# Connectors-MK2.net
KiCad netlist of a schematic drawn in EAGLE
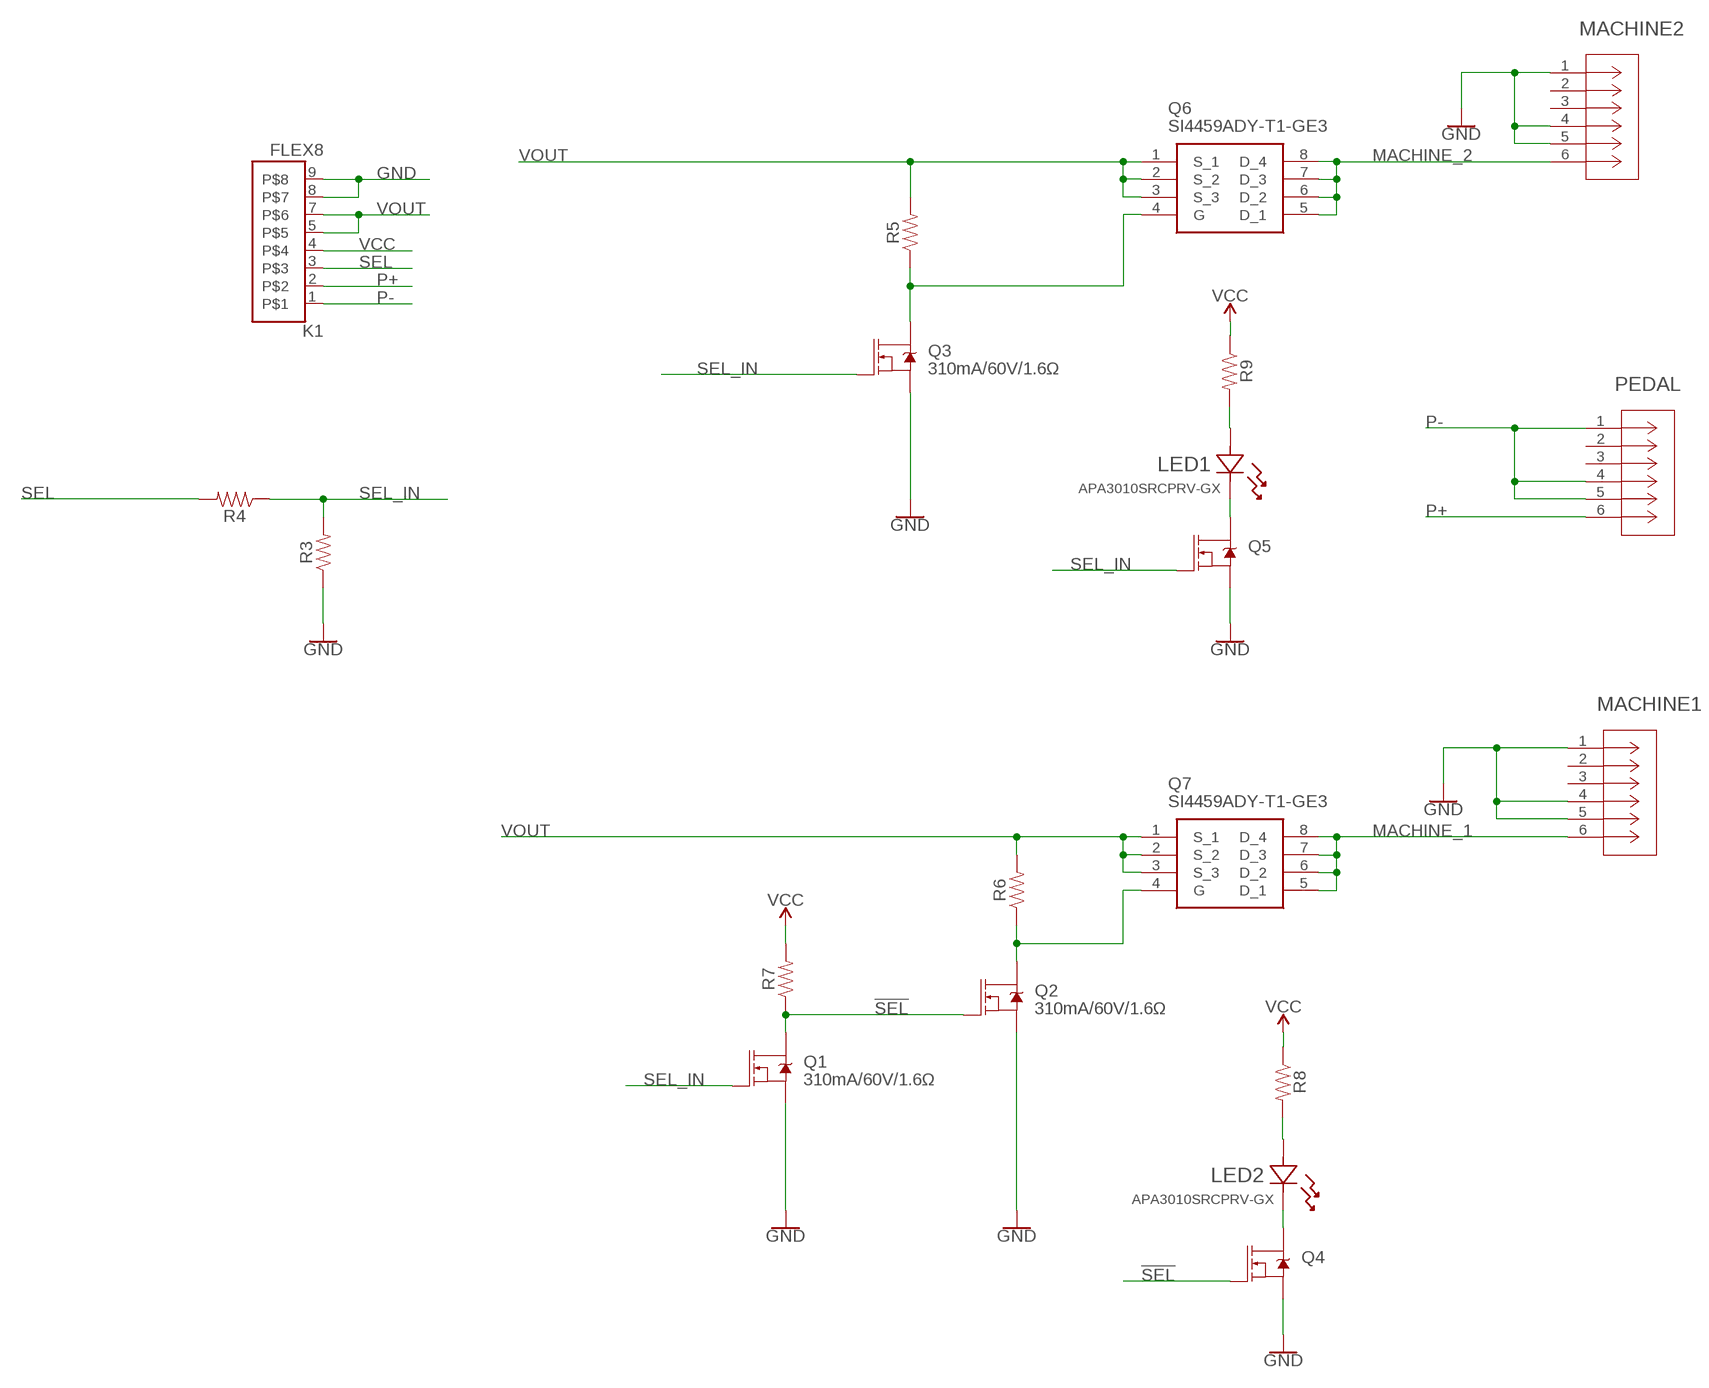
[diagram p0: schematic, sheet 1]

(export (version "E")
  (design (tool "Eeschema 10.0.6"))
  (components
    (comp (ref "K1")
      (value "FLEX8")
      (footprint "eagle-import:FLEX8")
      (libsource (lib "eagle-import") (part "FLEX8"))
    )
    (comp (ref "LED1")
      (value "APA3010SRCPRV-GX")
      (footprint "eagle-import:LED_APA3010SRCPRV-GX_KNB")
      (fields (field (name "COPYRIGHT") "Copyright (C) 2018 Accelerated Designs. All rights reserved"))
      (libsource (lib "eagle-import") (part "APA3010SRCPRV-GX"))
    )
    (comp (ref "LED2")
      (value "APA3010SRCPRV-GX")
      (footprint "eagle-import:LED_APA3010SRCPRV-GX_KNB")
      (fields (field (name "COPYRIGHT") "Copyright (C) 2018 Accelerated Designs. All rights reserved"))
      (libsource (lib "eagle-import") (part "APA3010SRCPRV-GX"))
    )
    (comp (ref "MACHINE1")
      (value "ACJS-MHDR")
      (footprint "eagle-import:CONN_MHDR_AMP")
      (fields (field (name "COPYRIGHT") "Copyright (C) 2018 Accelerated Designs. All rights reserved"))
      (libsource (lib "eagle-import") (part "ACJS-MHDR"))
    )
    (comp (ref "MACHINE2")
      (value "ACJS-MHDR")
      (footprint "eagle-import:CONN_MHDR_AMP")
      (fields (field (name "COPYRIGHT") "Copyright (C) 2018 Accelerated Designs. All rights reserved"))
      (libsource (lib "eagle-import") (part "ACJS-MHDR"))
    )
    (comp (ref "PEDAL")
      (value "ACJS-MHDR")
      (footprint "eagle-import:CONN_MHDR_AMP")
      (fields (field (name "COPYRIGHT") "Copyright (C) 2018 Accelerated Designs. All rights reserved"))
      (libsource (lib "eagle-import") (part "ACJS-MHDR"))
    )
    (comp (ref "Q1")
      (value "310mA/60V/1.6Ω")
      (footprint "eagle-import:SOT323")
      (libsource (lib "eagle-import") (part "MOSFET-NCH-2N7002PW"))
    )
    (comp (ref "Q2")
      (value "310mA/60V/1.6Ω")
      (footprint "eagle-import:SOT323")
      (libsource (lib "eagle-import") (part "MOSFET-NCH-2N7002PW"))
    )
    (comp (ref "Q3")
      (value "310mA/60V/1.6Ω")
      (footprint "eagle-import:SOT323")
      (libsource (lib "eagle-import") (part "MOSFET-NCH-2N7002PW"))
    )
    (comp (ref "Q4")
      (value "310mA/60V/1.6Ω")
      (footprint "eagle-import:SOT323")
      (libsource (lib "eagle-import") (part "MOSFET-NCH-2N7002PW"))
    )
    (comp (ref "Q5")
      (value "310mA/60V/1.6Ω")
      (footprint "eagle-import:SOT323")
      (libsource (lib "eagle-import") (part "MOSFET-NCH-2N7002PW"))
    )
    (comp (ref "Q6")
      (value "SI4459ADY-T1-GE3")
      (footprint "eagle-import:SOIC127P600X175-8N")
      (fields (field (name "MOUSER_PART_NUMBER") "781-SI4459ADY-T1-GE3"))
      (libsource (lib "eagle-import") (part "SI4459ADY-T1-GE3"))
    )
    (comp (ref "Q7")
      (value "SI4459ADY-T1-GE3")
      (footprint "eagle-import:SOIC127P600X175-8N")
      (fields (field (name "MOUSER_PART_NUMBER") "781-SI4459ADY-T1-GE3"))
      (libsource (lib "eagle-import") (part "SI4459ADY-T1-GE3"))
    )
    (comp (ref "R3")
      (value "RESISTOR0603")
      (footprint "eagle-import:0603")
      (libsource (lib "eagle-import") (part "RESISTOR0603"))
    )
    (comp (ref "R4")
      (value "RESISTOR0603")
      (footprint "eagle-import:0603")
      (libsource (lib "eagle-import") (part "RESISTOR0603"))
    )
    (comp (ref "R5")
      (value "RESISTOR0603")
      (footprint "eagle-import:0603")
      (libsource (lib "eagle-import") (part "RESISTOR0603"))
    )
    (comp (ref "R6")
      (value "RESISTOR0603")
      (footprint "eagle-import:0603")
      (libsource (lib "eagle-import") (part "RESISTOR0603"))
    )
    (comp (ref "R7")
      (value "RESISTOR0603")
      (footprint "eagle-import:0603")
      (libsource (lib "eagle-import") (part "RESISTOR0603"))
    )
    (comp (ref "R8")
      (value "RESISTOR0805")
      (footprint "eagle-import:0805")
      (libsource (lib "eagle-import") (part "RESISTOR0805"))
    )
    (comp (ref "R9")
      (value "RESISTOR0805")
      (footprint "eagle-import:0805")
      (libsource (lib "eagle-import") (part "RESISTOR0805"))
    )
  )
  (nets
    (net (code "1") (name "/MACHINE_1") (class "Default")
      (node (ref "MACHINE1") (pin "6") (pinfunction "6_6") (pintype "passive"))
      (node (ref "Q7") (pin "5") (pinfunction "D_1_5") (pintype "bidirectional"))
      (node (ref "Q7") (pin "6") (pinfunction "D_2_6") (pintype "bidirectional"))
      (node (ref "Q7") (pin "7") (pinfunction "D_3_7") (pintype "bidirectional"))
      (node (ref "Q7") (pin "8") (pinfunction "D_4_8") (pintype "bidirectional"))
    )
    (net (code "2") (name "/MACHINE_2") (class "Default")
      (node (ref "MACHINE2") (pin "6") (pinfunction "6_6") (pintype "passive"))
      (node (ref "Q6") (pin "5") (pinfunction "D_1_5") (pintype "bidirectional"))
      (node (ref "Q6") (pin "6") (pinfunction "D_2_6") (pintype "bidirectional"))
      (node (ref "Q6") (pin "7") (pinfunction "D_3_7") (pintype "bidirectional"))
      (node (ref "Q6") (pin "8") (pinfunction "D_4_8") (pintype "bidirectional"))
    )
    (net (code "3") (name "/P+") (class "Default")
      (node (ref "K1") (pin "2") (pinfunction "P$2_2") (pintype "bidirectional"))
      (node (ref "PEDAL") (pin "6") (pinfunction "6_6") (pintype "passive"))
    )
    (net (code "4") (name "/P-") (class "Default")
      (node (ref "K1") (pin "1") (pinfunction "P$1_1") (pintype "bidirectional"))
      (node (ref "PEDAL") (pin "1") (pinfunction "1_1") (pintype "passive"))
      (node (ref "PEDAL") (pin "4") (pinfunction "4_4") (pintype "passive"))
      (node (ref "PEDAL") (pin "5") (pinfunction "5_5") (pintype "passive"))
    )
    (net (code "5") (name "/SEL") (class "Default")
      (node (ref "K1") (pin "3") (pinfunction "P$3_3") (pintype "bidirectional"))
      (node (ref "R4") (pin "2") (pinfunction "2_2") (pintype "passive"))
    )
    (net (code "6") (name "/SEL_IN") (class "Default")
      (node (ref "Q1") (pin "1") (pinfunction "G_1") (pintype "bidirectional"))
      (node (ref "Q3") (pin "1") (pinfunction "G_1") (pintype "bidirectional"))
      (node (ref "Q5") (pin "1") (pinfunction "G_1") (pintype "bidirectional"))
      (node (ref "R3") (pin "2") (pinfunction "2_2") (pintype "passive"))
      (node (ref "R4") (pin "1") (pinfunction "1_1") (pintype "passive"))
    )
    (net (code "7") (name "/VOUT") (class "Default")
      (node (ref "K1") (pin "5") (pinfunction "P$5_5") (pintype "bidirectional"))
      (node (ref "K1") (pin "7") (pinfunction "P$6_7") (pintype "bidirectional"))
      (node (ref "Q6") (pin "1") (pinfunction "S_1_1") (pintype "bidirectional"))
      (node (ref "Q6") (pin "2") (pinfunction "S_2_2") (pintype "bidirectional"))
      (node (ref "Q6") (pin "3") (pinfunction "S_3_3") (pintype "bidirectional"))
      (node (ref "Q7") (pin "1") (pinfunction "S_1_1") (pintype "bidirectional"))
      (node (ref "Q7") (pin "2") (pinfunction "S_2_2") (pintype "bidirectional"))
      (node (ref "Q7") (pin "3") (pinfunction "S_3_3") (pintype "bidirectional"))
      (node (ref "R5") (pin "2") (pinfunction "2_2") (pintype "passive"))
      (node (ref "R6") (pin "2") (pinfunction "2_2") (pintype "passive"))
    )
    (net (code "8") (name "/~{SEL}") (class "Default")
      (node (ref "Q1") (pin "3") (pinfunction "D_3") (pintype "bidirectional"))
      (node (ref "Q2") (pin "1") (pinfunction "G_1") (pintype "bidirectional"))
      (node (ref "Q4") (pin "1") (pinfunction "G_1") (pintype "bidirectional"))
      (node (ref "R7") (pin "1") (pinfunction "1_1") (pintype "passive"))
    )
    (net (code "9") (name "GND") (class "Default")
      (node (ref "K1") (pin "8") (pinfunction "P$7_8") (pintype "bidirectional"))
      (node (ref "K1") (pin "9") (pinfunction "P$8_9") (pintype "bidirectional"))
      (node (ref "MACHINE1") (pin "1") (pinfunction "1_1") (pintype "passive"))
      (node (ref "MACHINE1") (pin "4") (pinfunction "4_4") (pintype "passive"))
      (node (ref "MACHINE1") (pin "5") (pinfunction "5_5") (pintype "passive"))
      (node (ref "MACHINE2") (pin "1") (pinfunction "1_1") (pintype "passive"))
      (node (ref "MACHINE2") (pin "4") (pinfunction "4_4") (pintype "passive"))
      (node (ref "MACHINE2") (pin "5") (pinfunction "5_5") (pintype "passive"))
      (node (ref "Q1") (pin "2") (pinfunction "S_2") (pintype "bidirectional"))
      (node (ref "Q2") (pin "2") (pinfunction "S_2") (pintype "bidirectional"))
      (node (ref "Q3") (pin "2") (pinfunction "S_2") (pintype "bidirectional"))
      (node (ref "Q4") (pin "2") (pinfunction "S_2") (pintype "bidirectional"))
      (node (ref "Q5") (pin "2") (pinfunction "S_2") (pintype "bidirectional"))
      (node (ref "R3") (pin "1") (pinfunction "1_1") (pintype "passive"))
    )
    (net (code "10") (name "Net-(LED1-Pad2)") (class "Default")
      (node (ref "LED1") (pin "2") (pinfunction "2_2") (pintype "passive"))
      (node (ref "R9") (pin "2") (pinfunction "2_2") (pintype "passive"))
    )
    (net (code "11") (name "Net-(LED2-Pad2)") (class "Default")
      (node (ref "LED2") (pin "2") (pinfunction "2_2") (pintype "passive"))
      (node (ref "R8") (pin "2") (pinfunction "2_2") (pintype "passive"))
    )
    (net (code "12") (name "Net-(Q2-D)") (class "Default")
      (node (ref "Q2") (pin "3") (pinfunction "D_3") (pintype "bidirectional"))
      (node (ref "Q7") (pin "4") (pinfunction "G_4") (pintype "bidirectional"))
      (node (ref "R6") (pin "1") (pinfunction "1_1") (pintype "passive"))
    )
    (net (code "13") (name "Net-(Q3-D)") (class "Default")
      (node (ref "Q3") (pin "3") (pinfunction "D_3") (pintype "bidirectional"))
      (node (ref "Q6") (pin "4") (pinfunction "G_4") (pintype "bidirectional"))
      (node (ref "R5") (pin "1") (pinfunction "1_1") (pintype "passive"))
    )
    (net (code "14") (name "Net-(Q4-D)") (class "Default")
      (node (ref "LED2") (pin "1") (pinfunction "1_1") (pintype "passive"))
      (node (ref "Q4") (pin "3") (pinfunction "D_3") (pintype "bidirectional"))
    )
    (net (code "15") (name "Net-(Q5-D)") (class "Default")
      (node (ref "LED1") (pin "1") (pinfunction "1_1") (pintype "passive"))
      (node (ref "Q5") (pin "3") (pinfunction "D_3") (pintype "bidirectional"))
    )
    (net (code "16") (name "VCC") (class "Default")
      (node (ref "K1") (pin "4") (pinfunction "P$4_4") (pintype "bidirectional"))
      (node (ref "R7") (pin "2") (pinfunction "2_2") (pintype "passive"))
      (node (ref "R8") (pin "1") (pinfunction "1_1") (pintype "passive"))
      (node (ref "R9") (pin "1") (pinfunction "1_1") (pintype "passive"))
    )
    (net (code "17") (name "unconnected-(MACHINE1-Pad2)") (class "Default")
      (node (ref "MACHINE1") (pin "2") (pinfunction "2_2") (pintype "passive"))
    )
    (net (code "18") (name "unconnected-(MACHINE1-Pad3)") (class "Default")
      (node (ref "MACHINE1") (pin "3") (pinfunction "3_3") (pintype "passive"))
    )
    (net (code "19") (name "unconnected-(MACHINE2-Pad2)") (class "Default")
      (node (ref "MACHINE2") (pin "2") (pinfunction "2_2") (pintype "passive"))
    )
    (net (code "20") (name "unconnected-(MACHINE2-Pad3)") (class "Default")
      (node (ref "MACHINE2") (pin "3") (pinfunction "3_3") (pintype "passive"))
    )
    (net (code "21") (name "unconnected-(PEDAL-Pad2)") (class "Default")
      (node (ref "PEDAL") (pin "2") (pinfunction "2_2") (pintype "passive"))
    )
    (net (code "22") (name "unconnected-(PEDAL-Pad3)") (class "Default")
      (node (ref "PEDAL") (pin "3") (pinfunction "3_3") (pintype "passive"))
    )
  )
)
